# v1.net
KiCad netlist of a schematic drawn in EAGLE
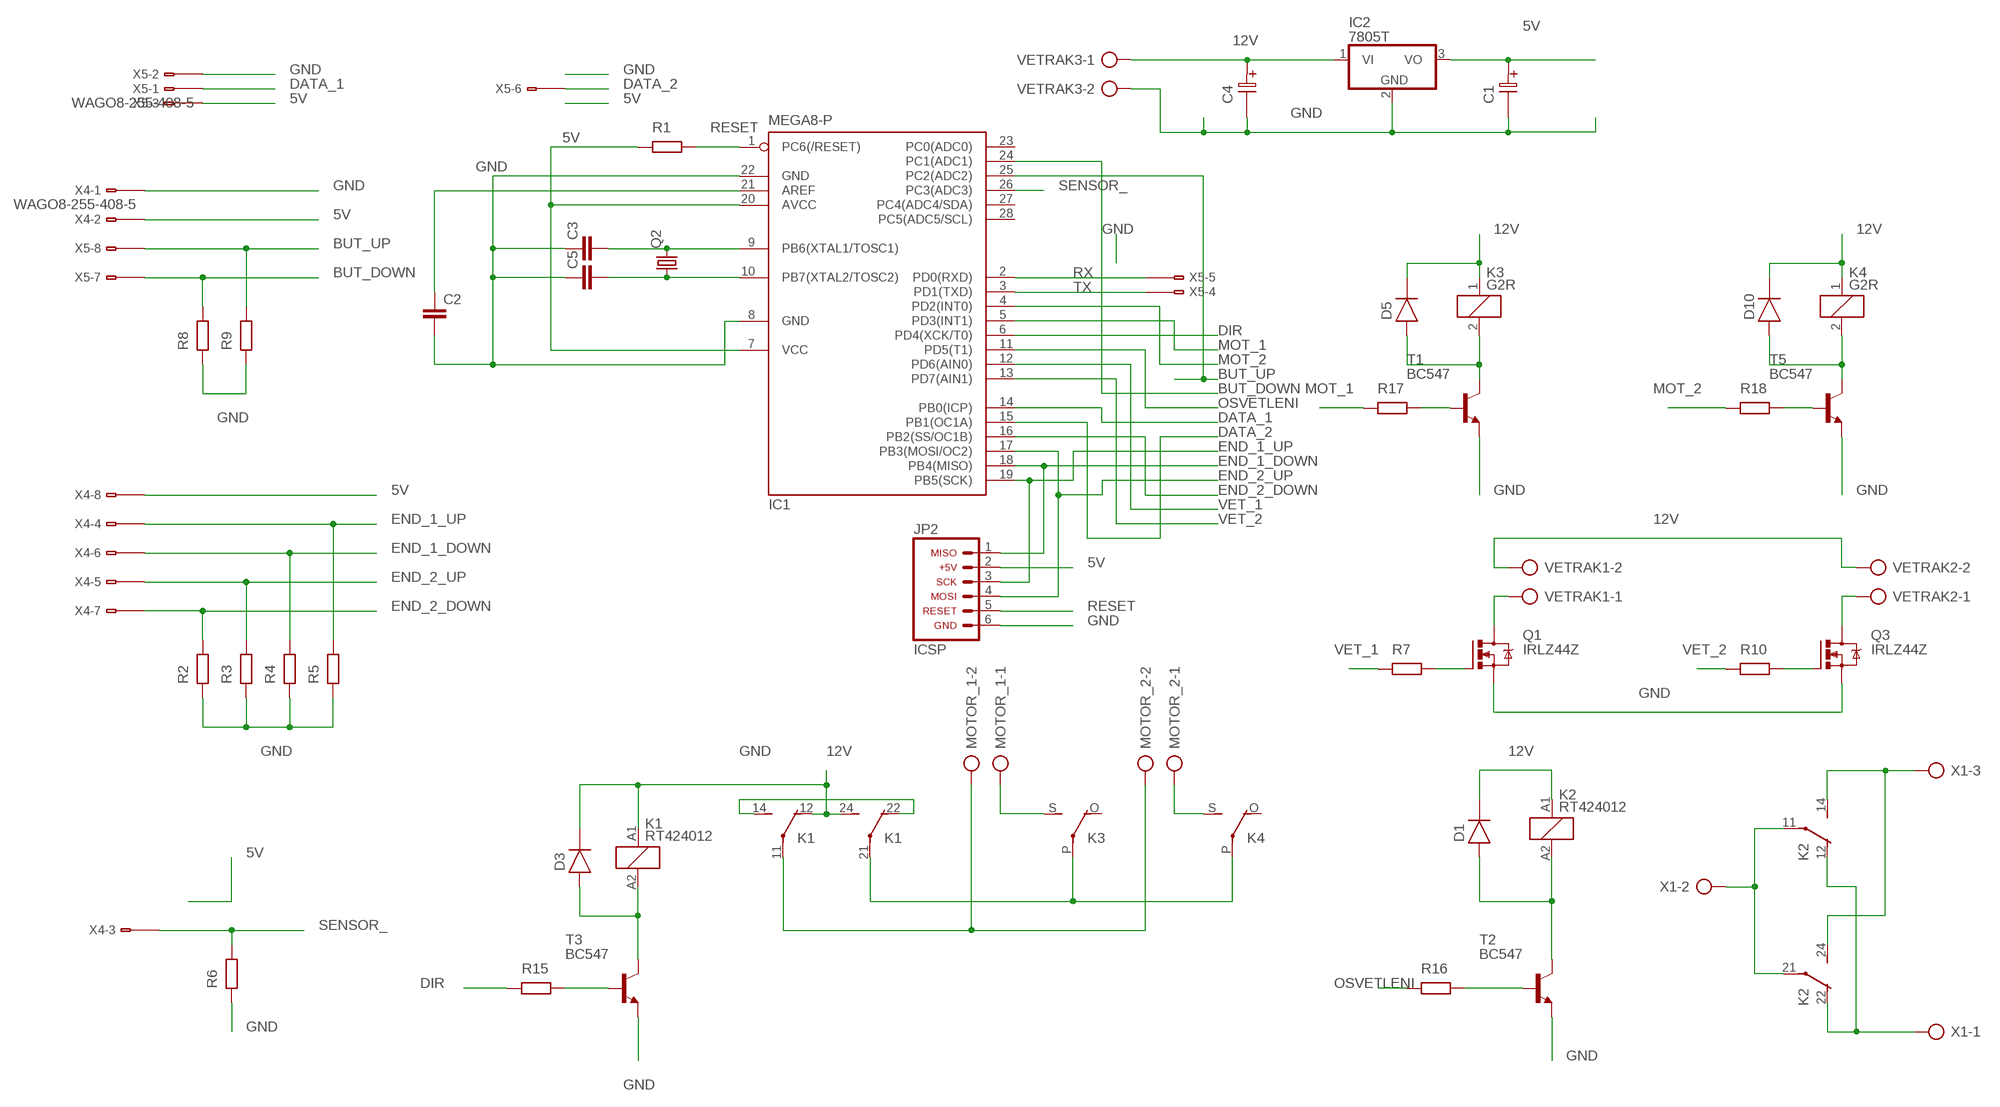
[diagram p0: schematic, sheet 1]

(export (version "E")
  (design (tool "Eeschema 10.0.6"))
  (components
    (comp (ref "C1")
      (value "CT12")
      (footprint "eagle-import:CT12")
      (libsource (lib "eagle-import") (part "CT12"))
    )
    (comp (ref "C2")
      (value "C-EU025-030X050")
      (footprint "eagle-import:C025-030X050")
      (libsource (lib "eagle-import") (part "C-EU025-030X050"))
    )
    (comp (ref "C3")
      (value "C-EU050-025X075")
      (footprint "eagle-import:C050-025X075")
      (libsource (lib "eagle-import") (part "C-EU050-025X075"))
    )
    (comp (ref "C4")
      (value "CT12")
      (footprint "eagle-import:CT12")
      (libsource (lib "eagle-import") (part "CT12"))
    )
    (comp (ref "C5")
      (value "C-EU050-025X075")
      (footprint "eagle-import:C050-025X075")
      (libsource (lib "eagle-import") (part "C-EU050-025X075"))
    )
    (comp (ref "D1")
      (value "1N4007")
      (footprint "eagle-import:DO41")
      (libsource (lib "eagle-import") (part "1N4007"))
    )
    (comp (ref "D3")
      (value "1N4007")
      (footprint "eagle-import:DO41")
      (libsource (lib "eagle-import") (part "1N4007"))
    )
    (comp (ref "D5")
      (value "1N4007")
      (footprint "eagle-import:DO41")
      (libsource (lib "eagle-import") (part "1N4007"))
    )
    (comp (ref "D10")
      (value "1N4007")
      (footprint "eagle-import:DO41")
      (libsource (lib "eagle-import") (part "1N4007"))
    )
    (comp (ref "IC1")
      (value "MEGA8-P")
      (footprint "eagle-import:DIL28-3")
      (libsource (lib "eagle-import") (part "MEGA8-P"))
    )
    (comp (ref "IC2")
      (value "7805T")
      (footprint "eagle-import:TO220H")
      (libsource (lib "eagle-import") (part "78T05"))
    )
    (comp (ref "JP2")
      (value "ARDUINO_CONN-ICSP")
      (footprint "eagle-import:CONN-2X03")
      (libsource (lib "eagle-import") (part "ARDUINO_CONN-ICSP"))
    )
    (comp (ref "K1")
      (value "RT424012")
      (footprint "eagle-import:RT2C_O")
      (libsource (lib "eagle-import") (part "RT42?4012"))
    )
    (comp (ref "K2")
      (value "RT424012")
      (footprint "eagle-import:RT2C_O")
      (libsource (lib "eagle-import") (part "RT42?4012"))
    )
    (comp (ref "K3")
      (value "G2R")
      (footprint "eagle-import:G2R")
      (libsource (lib "eagle-import") (part "G2R"))
    )
    (comp (ref "K4")
      (value "G2R")
      (footprint "eagle-import:G2R")
      (libsource (lib "eagle-import") (part "G2R"))
    )
    (comp (ref "MOTOR_1")
      (value "AK500/2")
      (footprint "eagle-import:AK500_2")
      (libsource (lib "eagle-import") (part "AK500/2"))
    )
    (comp (ref "MOTOR_2")
      (value "AK500/2")
      (footprint "eagle-import:AK500_2")
      (libsource (lib "eagle-import") (part "AK500/2"))
    )
    (comp (ref "Q1")
      (value "IRLZ44Z")
      (footprint "eagle-import:TO220BH")
      (libsource (lib "eagle-import") (part "IRLZ44Z"))
    )
    (comp (ref "Q2")
      (value "CRYSTALHC49S")
      (footprint "eagle-import:HC49_S")
      (libsource (lib "eagle-import") (part "CRYSTALHC49S"))
    )
    (comp (ref "Q3")
      (value "IRLZ44Z")
      (footprint "eagle-import:TO220BH")
      (libsource (lib "eagle-import") (part "IRLZ44Z"))
    )
    (comp (ref "R1") (value "RR") (footprint "eagle-import:RR") (libsource (lib "eagle-import") (part "RR")))
    (comp (ref "R2") (value "RR") (footprint "eagle-import:RR") (libsource (lib "eagle-import") (part "RR")))
    (comp (ref "R3") (value "RR") (footprint "eagle-import:RR") (libsource (lib "eagle-import") (part "RR")))
    (comp (ref "R4") (value "RR") (footprint "eagle-import:RR") (libsource (lib "eagle-import") (part "RR")))
    (comp (ref "R5") (value "RR") (footprint "eagle-import:RR") (libsource (lib "eagle-import") (part "RR")))
    (comp (ref "R6") (value "RR") (footprint "eagle-import:RR") (libsource (lib "eagle-import") (part "RR")))
    (comp (ref "R7") (value "RR") (footprint "eagle-import:RR") (libsource (lib "eagle-import") (part "RR")))
    (comp (ref "R8") (value "RR") (footprint "eagle-import:RR") (libsource (lib "eagle-import") (part "RR")))
    (comp (ref "R9") (value "RR") (footprint "eagle-import:RR") (libsource (lib "eagle-import") (part "RR")))
    (comp (ref "R10") (value "RR") (footprint "eagle-import:RR") (libsource (lib "eagle-import") (part "RR")))
    (comp (ref "R15") (value "RR") (footprint "eagle-import:RR") (libsource (lib "eagle-import") (part "RR")))
    (comp (ref "R16") (value "RR") (footprint "eagle-import:RR") (libsource (lib "eagle-import") (part "RR")))
    (comp (ref "R17") (value "RR") (footprint "eagle-import:RR") (libsource (lib "eagle-import") (part "RR")))
    (comp (ref "R18") (value "RR") (footprint "eagle-import:RR") (libsource (lib "eagle-import") (part "RR")))
    (comp (ref "T1")
      (value "BC547")
      (footprint "eagle-import:TO92")
      (libsource (lib "eagle-import") (part "BC547"))
    )
    (comp (ref "T2")
      (value "BC547")
      (footprint "eagle-import:TO92")
      (libsource (lib "eagle-import") (part "BC547"))
    )
    (comp (ref "T3")
      (value "BC547")
      (footprint "eagle-import:TO92")
      (libsource (lib "eagle-import") (part "BC547"))
    )
    (comp (ref "T5")
      (value "BC547")
      (footprint "eagle-import:TO92")
      (libsource (lib "eagle-import") (part "BC547"))
    )
    (comp (ref "VETRAK1")
      (value "AK500/2")
      (footprint "eagle-import:AK500_2")
      (libsource (lib "eagle-import") (part "AK500/2"))
    )
    (comp (ref "VETRAK2")
      (value "AK500/2")
      (footprint "eagle-import:AK500_2")
      (libsource (lib "eagle-import") (part "AK500/2"))
    )
    (comp (ref "VETRAK3")
      (value "AK500/2")
      (footprint "eagle-import:AK500_2")
      (libsource (lib "eagle-import") (part "AK500/2"))
    )
    (comp (ref "X1")
      (value "AK500/3-H")
      (footprint "eagle-import:AK500_3-H")
      (libsource (lib "eagle-import") (part "AK500/3-H"))
    )
    (comp (ref "X4")
      (value "WAGO8-255-408-5")
      (footprint "eagle-import:255-408-5")
      (fields (field (name "MPN") "255-408"))
      (libsource (lib "eagle-import") (part "WAGO8-255-408-5"))
    )
    (comp (ref "X5")
      (value "WAGO8-255-408-5")
      (footprint "eagle-import:255-408-5")
      (fields (field (name "MPN") "255-408"))
      (libsource (lib "eagle-import") (part "WAGO8-255-408-5"))
    )
  )
  (nets
    (net (code "1") (name "/5V") (class "Default")
      (node (ref "C1") (pin "1") (pinfunction "1_1") (pintype "passive"))
      (node (ref "IC1") (pin "20") (pinfunction "AVCC_20") (pintype "power_in"))
      (node (ref "IC1") (pin "7") (pinfunction "VCC_7") (pintype "power_in"))
      (node (ref "IC2") (pin "3") (pinfunction "VO_3") (pintype "passive"))
      (node (ref "JP2") (pin "2") (pinfunction "2_2") (pintype "passive"))
      (node (ref "R1") (pin "1") (pinfunction "1_1") (pintype "passive"))
      (node (ref "X4") (pin "B2") (pinfunction "B1_B2") (pintype "passive"))
      (node (ref "X4") (pin "B8") (pinfunction "B1_B8") (pintype "passive"))
      (node (ref "X5") (pin "B3") (pinfunction "B1_B3") (pintype "passive"))
    )
    (net (code "2") (name "/12V") (class "Default")
      (node (ref "C4") (pin "1") (pinfunction "1_1") (pintype "passive"))
      (node (ref "D1") (pin "K") (pinfunction "K_K") (pintype "passive"))
      (node (ref "D10") (pin "K") (pinfunction "K_K") (pintype "passive"))
      (node (ref "D3") (pin "K") (pinfunction "K_K") (pintype "passive"))
      (node (ref "D5") (pin "K") (pinfunction "K_K") (pintype "passive"))
      (node (ref "IC2") (pin "1") (pinfunction "VI_1") (pintype "input"))
      (node (ref "K1") (pin "12") (pinfunction "O_12") (pintype "passive"))
      (node (ref "K1") (pin "24") (pinfunction "S_24") (pintype "passive"))
      (node (ref "K1") (pin "A1") (pinfunction "1_A1") (pintype "passive"))
      (node (ref "K2") (pin "A1") (pinfunction "1_A1") (pintype "passive"))
      (node (ref "K3") (pin "1") (pinfunction "1_1") (pintype "passive"))
      (node (ref "K4") (pin "1") (pinfunction "1_1") (pintype "passive"))
      (node (ref "VETRAK1") (pin "2") (pinfunction "KL_2") (pintype "passive"))
      (node (ref "VETRAK2") (pin "2") (pinfunction "KL_2") (pintype "passive"))
      (node (ref "VETRAK3") (pin "1") (pinfunction "KL_1") (pintype "passive"))
    )
    (net (code "3") (name "/BUT_DOWN") (class "Default")
      (node (ref "IC1") (pin "24") (pinfunction "PC1(ADC1)_24") (pintype "bidirectional"))
      (node (ref "R8") (pin "2") (pinfunction "2_2") (pintype "passive"))
      (node (ref "X5") (pin "B7") (pinfunction "B1_B7") (pintype "passive"))
    )
    (net (code "4") (name "/BUT_UP") (class "Default")
      (node (ref "IC1") (pin "25") (pinfunction "PC2(ADC2)_25") (pintype "bidirectional"))
      (node (ref "R9") (pin "2") (pinfunction "2_2") (pintype "passive"))
      (node (ref "X5") (pin "B8") (pinfunction "B1_B8") (pintype "passive"))
    )
    (net (code "5") (name "/DATA_1") (class "Default")
      (node (ref "IC1") (pin "14") (pinfunction "PB0(ICP)_14") (pintype "bidirectional"))
      (node (ref "X5") (pin "B1") (pinfunction "B1_B1") (pintype "passive"))
    )
    (net (code "6") (name "/DATA_2") (class "Default")
      (node (ref "IC1") (pin "15") (pinfunction "PB1(OC1A)_15") (pintype "bidirectional"))
      (node (ref "X5") (pin "B6") (pinfunction "B1_B6") (pintype "passive"))
    )
    (net (code "7") (name "/DIR") (class "Default")
      (node (ref "IC1") (pin "6") (pinfunction "PD4(XCK/T0)_6") (pintype "bidirectional"))
      (node (ref "R15") (pin "1") (pinfunction "1_1") (pintype "passive"))
    )
    (net (code "8") (name "/END_1_DOWN") (class "Default")
      (node (ref "IC1") (pin "18") (pinfunction "PB4(MISO)_18") (pintype "bidirectional"))
      (node (ref "JP2") (pin "1") (pinfunction "1_1") (pintype "passive"))
      (node (ref "R4") (pin "2") (pinfunction "2_2") (pintype "passive"))
      (node (ref "X4") (pin "B6") (pinfunction "B1_B6") (pintype "passive"))
    )
    (net (code "9") (name "/END_1_UP") (class "Default")
      (node (ref "IC1") (pin "19") (pinfunction "PB5(SCK)_19") (pintype "bidirectional"))
      (node (ref "JP2") (pin "3") (pinfunction "3_3") (pintype "passive"))
      (node (ref "R5") (pin "2") (pinfunction "2_2") (pintype "passive"))
      (node (ref "X4") (pin "B4") (pinfunction "B1_B4") (pintype "passive"))
    )
    (net (code "10") (name "/END_2_DOWN") (class "Default")
      (node (ref "IC1") (pin "16") (pinfunction "PB2(SS/OC1B)_16") (pintype "bidirectional"))
      (node (ref "R2") (pin "2") (pinfunction "2_2") (pintype "passive"))
      (node (ref "X4") (pin "B7") (pinfunction "B1_B7") (pintype "passive"))
    )
    (net (code "11") (name "/END_2_UP") (class "Default")
      (node (ref "IC1") (pin "17") (pinfunction "PB3(MOSI/OC2)_17") (pintype "bidirectional"))
      (node (ref "JP2") (pin "4") (pinfunction "4_4") (pintype "passive"))
      (node (ref "R3") (pin "2") (pinfunction "2_2") (pintype "passive"))
      (node (ref "X4") (pin "B5") (pinfunction "B1_B5") (pintype "passive"))
    )
    (net (code "12") (name "/GND") (class "Default")
      (node (ref "C1") (pin "2") (pinfunction "2_2") (pintype "passive"))
      (node (ref "C2") (pin "2") (pinfunction "2_2") (pintype "passive"))
      (node (ref "C3") (pin "1") (pinfunction "1_1") (pintype "passive"))
      (node (ref "C4") (pin "2") (pinfunction "2_2") (pintype "passive"))
      (node (ref "C5") (pin "1") (pinfunction "1_1") (pintype "passive"))
      (node (ref "IC1") (pin "22") (pinfunction "GND_22") (pintype "power_in"))
      (node (ref "IC1") (pin "8") (pinfunction "GND_8") (pintype "power_in"))
      (node (ref "IC2") (pin "2") (pinfunction "GND_2") (pintype "passive"))
      (node (ref "JP2") (pin "6") (pinfunction "6_6") (pintype "passive"))
      (node (ref "K1") (pin "14") (pinfunction "S_14") (pintype "passive"))
      (node (ref "K1") (pin "22") (pinfunction "O_22") (pintype "passive"))
      (node (ref "Q1") (pin "S") (pinfunction "S_S") (pintype "passive"))
      (node (ref "Q3") (pin "S") (pinfunction "S_S") (pintype "passive"))
      (node (ref "R2") (pin "1") (pinfunction "1_1") (pintype "passive"))
      (node (ref "R3") (pin "1") (pinfunction "1_1") (pintype "passive"))
      (node (ref "R4") (pin "1") (pinfunction "1_1") (pintype "passive"))
      (node (ref "R5") (pin "1") (pinfunction "1_1") (pintype "passive"))
      (node (ref "R6") (pin "1") (pinfunction "1_1") (pintype "passive"))
      (node (ref "R8") (pin "1") (pinfunction "1_1") (pintype "passive"))
      (node (ref "R9") (pin "1") (pinfunction "1_1") (pintype "passive"))
      (node (ref "T1") (pin "1") (pinfunction "E_1") (pintype "passive"))
      (node (ref "T2") (pin "1") (pinfunction "E_1") (pintype "passive"))
      (node (ref "T3") (pin "1") (pinfunction "E_1") (pintype "passive"))
      (node (ref "T5") (pin "1") (pinfunction "E_1") (pintype "passive"))
      (node (ref "VETRAK3") (pin "2") (pinfunction "KL_2") (pintype "passive"))
      (node (ref "X4") (pin "B1") (pinfunction "B1_B1") (pintype "passive"))
      (node (ref "X5") (pin "B2") (pinfunction "B1_B2") (pintype "passive"))
    )
    (net (code "13") (name "/MOT_1") (class "Default")
      (node (ref "IC1") (pin "5") (pinfunction "PD3(INT1)_5") (pintype "bidirectional"))
      (node (ref "R17") (pin "1") (pinfunction "1_1") (pintype "passive"))
    )
    (net (code "14") (name "/MOT_2") (class "Default")
      (node (ref "IC1") (pin "4") (pinfunction "PD2(INT0)_4") (pintype "bidirectional"))
      (node (ref "R18") (pin "1") (pinfunction "1_1") (pintype "passive"))
    )
    (net (code "15") (name "/OSVETLENI") (class "Default")
      (node (ref "IC1") (pin "11") (pinfunction "PD5(T1)_11") (pintype "bidirectional"))
      (node (ref "R16") (pin "1") (pinfunction "1_1") (pintype "passive"))
    )
    (net (code "16") (name "/RESET") (class "Default")
      (node (ref "IC1") (pin "1") (pinfunction "PC6(/RESET)_1") (pintype "bidirectional"))
      (node (ref "JP2") (pin "5") (pinfunction "5_5") (pintype "passive"))
      (node (ref "R1") (pin "2") (pinfunction "2_2") (pintype "passive"))
    )
    (net (code "17") (name "/RX") (class "Default")
      (node (ref "IC1") (pin "2") (pinfunction "PD0(RXD)_2") (pintype "bidirectional"))
      (node (ref "X5") (pin "B5") (pinfunction "B1_B5") (pintype "passive"))
    )
    (net (code "18") (name "/SENSOR_") (class "Default")
      (node (ref "IC1") (pin "26") (pinfunction "PC3(ADC3)_26") (pintype "bidirectional"))
      (node (ref "R6") (pin "2") (pinfunction "2_2") (pintype "passive"))
      (node (ref "X4") (pin "B3") (pinfunction "B1_B3") (pintype "passive"))
    )
    (net (code "19") (name "/TX") (class "Default")
      (node (ref "IC1") (pin "3") (pinfunction "PD1(TXD)_3") (pintype "bidirectional"))
      (node (ref "X5") (pin "B4") (pinfunction "B1_B4") (pintype "passive"))
    )
    (net (code "20") (name "/VET_1") (class "Default")
      (node (ref "IC1") (pin "12") (pinfunction "PD6(AIN0)_12") (pintype "bidirectional"))
      (node (ref "R7") (pin "1") (pinfunction "1_1") (pintype "passive"))
    )
    (net (code "21") (name "/VET_2") (class "Default")
      (node (ref "IC1") (pin "13") (pinfunction "PD7(AIN1)_13") (pintype "bidirectional"))
      (node (ref "R10") (pin "1") (pinfunction "1_1") (pintype "passive"))
    )
    (net (code "22") (name "Net-(IC1-AREF)") (class "Default")
      (node (ref "C2") (pin "1") (pinfunction "1_1") (pintype "passive"))
      (node (ref "IC1") (pin "21") (pinfunction "AREF_21") (pintype "passive"))
    )
    (net (code "23") (name "Net-(IC1-PB6(XTAL1{slash}TOSC1))") (class "Default")
      (node (ref "C3") (pin "2") (pinfunction "2_2") (pintype "passive"))
      (node (ref "IC1") (pin "9") (pinfunction "PB6(XTAL1/TOSC1)_9") (pintype "bidirectional"))
      (node (ref "Q2") (pin "2") (pinfunction "2_2") (pintype "passive"))
    )
    (net (code "24") (name "Net-(IC1-PB7(XTAL2{slash}TOSC2))") (class "Default")
      (node (ref "C5") (pin "2") (pinfunction "2_2") (pintype "passive"))
      (node (ref "IC1") (pin "10") (pinfunction "PB7(XTAL2/TOSC2)_10") (pintype "bidirectional"))
      (node (ref "Q2") (pin "1") (pinfunction "1_1") (pintype "passive"))
    )
    (net (code "25") (name "Net-(K1A-2)") (class "Default")
      (node (ref "D3") (pin "A") (pinfunction "A_A") (pintype "passive"))
      (node (ref "K1") (pin "A2") (pinfunction "2_A2") (pintype "passive"))
      (node (ref "T3") (pin "3") (pinfunction "C_3") (pintype "passive"))
    )
    (net (code "26") (name "Net-(K1B-P)") (class "Default")
      (node (ref "K1") (pin "11") (pinfunction "P_11") (pintype "passive"))
      (node (ref "MOTOR_1") (pin "2") (pinfunction "KL_2") (pintype "passive"))
      (node (ref "MOTOR_2") (pin "2") (pinfunction "KL_2") (pintype "passive"))
    )
    (net (code "27") (name "Net-(K1C-P)") (class "Default")
      (node (ref "K1") (pin "21") (pinfunction "P_21") (pintype "passive"))
      (node (ref "K3") (pin "P") (pinfunction "P_P") (pintype "passive"))
      (node (ref "K4") (pin "P") (pinfunction "P_P") (pintype "passive"))
    )
    (net (code "28") (name "Net-(K2A-2)") (class "Default")
      (node (ref "D1") (pin "A") (pinfunction "A_A") (pintype "passive"))
      (node (ref "K2") (pin "A2") (pinfunction "2_A2") (pintype "passive"))
      (node (ref "T2") (pin "3") (pinfunction "C_3") (pintype "passive"))
    )
    (net (code "29") (name "Net-(K2B-O)") (class "Default")
      (node (ref "K2") (pin "12") (pinfunction "O_12") (pintype "passive"))
      (node (ref "K2") (pin "22") (pinfunction "O_22") (pintype "passive"))
      (node (ref "X1") (pin "1") (pinfunction "KL_1") (pintype "passive"))
    )
    (net (code "30") (name "Net-(K2B-P)") (class "Default")
      (node (ref "K2") (pin "11") (pinfunction "P_11") (pintype "passive"))
      (node (ref "K2") (pin "21") (pinfunction "P_21") (pintype "passive"))
      (node (ref "X1") (pin "2") (pinfunction "KL_2") (pintype "passive"))
    )
    (net (code "31") (name "Net-(K2B-S)") (class "Default")
      (node (ref "K2") (pin "14") (pinfunction "S_14") (pintype "passive"))
      (node (ref "K2") (pin "24") (pinfunction "S_24") (pintype "passive"))
      (node (ref "X1") (pin "3") (pinfunction "KL_3") (pintype "passive"))
    )
    (net (code "32") (name "Net-(MOTOR_1A-KL)") (class "Default")
      (node (ref "K3") (pin "S") (pinfunction "S_S") (pintype "passive"))
      (node (ref "MOTOR_1") (pin "1") (pinfunction "KL_1") (pintype "passive"))
    )
    (net (code "33") (name "Net-(MOTOR_2A-KL)") (class "Default")
      (node (ref "K4") (pin "S") (pinfunction "S_S") (pintype "passive"))
      (node (ref "MOTOR_2") (pin "1") (pinfunction "KL_1") (pintype "passive"))
    )
    (net (code "34") (name "Net-(Q1-PadG)") (class "Default")
      (node (ref "Q1") (pin "G") (pinfunction "G_G") (pintype "passive"))
      (node (ref "R7") (pin "2") (pinfunction "2_2") (pintype "passive"))
    )
    (net (code "35") (name "Net-(Q3-PadG)") (class "Default")
      (node (ref "Q3") (pin "G") (pinfunction "G_G") (pintype "passive"))
      (node (ref "R10") (pin "2") (pinfunction "2_2") (pintype "passive"))
    )
    (net (code "36") (name "Net-(T1-B)") (class "Default")
      (node (ref "R17") (pin "2") (pinfunction "2_2") (pintype "passive"))
      (node (ref "T1") (pin "2") (pinfunction "B_2") (pintype "passive"))
    )
    (net (code "37") (name "Net-(T1-C)") (class "Default")
      (node (ref "D5") (pin "A") (pinfunction "A_A") (pintype "passive"))
      (node (ref "K3") (pin "2") (pinfunction "2_2") (pintype "passive"))
      (node (ref "T1") (pin "3") (pinfunction "C_3") (pintype "passive"))
    )
    (net (code "38") (name "Net-(T2-B)") (class "Default")
      (node (ref "R16") (pin "2") (pinfunction "2_2") (pintype "passive"))
      (node (ref "T2") (pin "2") (pinfunction "B_2") (pintype "passive"))
    )
    (net (code "39") (name "Net-(T3-B)") (class "Default")
      (node (ref "R15") (pin "2") (pinfunction "2_2") (pintype "passive"))
      (node (ref "T3") (pin "2") (pinfunction "B_2") (pintype "passive"))
    )
    (net (code "40") (name "Net-(T5-B)") (class "Default")
      (node (ref "R18") (pin "2") (pinfunction "2_2") (pintype "passive"))
      (node (ref "T5") (pin "2") (pinfunction "B_2") (pintype "passive"))
    )
    (net (code "41") (name "Net-(T5-C)") (class "Default")
      (node (ref "D10") (pin "A") (pinfunction "A_A") (pintype "passive"))
      (node (ref "K4") (pin "2") (pinfunction "2_2") (pintype "passive"))
      (node (ref "T5") (pin "3") (pinfunction "C_3") (pintype "passive"))
    )
    (net (code "42") (name "Net-(VETRAK1A-KL)") (class "Default")
      (node (ref "Q1") (pin "D") (pinfunction "D_D") (pintype "passive"))
      (node (ref "VETRAK1") (pin "1") (pinfunction "KL_1") (pintype "passive"))
    )
    (net (code "43") (name "Net-(VETRAK2A-KL)") (class "Default")
      (node (ref "Q3") (pin "D") (pinfunction "D_D") (pintype "passive"))
      (node (ref "VETRAK2") (pin "1") (pinfunction "KL_1") (pintype "passive"))
    )
    (net (code "44") (name "unconnected-(IC1-PC0(ADC0)-Pad23)") (class "Default")
      (node (ref "IC1") (pin "23") (pinfunction "PC0(ADC0)_23") (pintype "bidirectional"))
    )
    (net (code "45") (name "unconnected-(IC1-PC4(ADC4{slash}SDA)-Pad27)") (class "Default")
      (node (ref "IC1") (pin "27") (pinfunction "PC4(ADC4/SDA)_27") (pintype "bidirectional"))
    )
    (net (code "46") (name "unconnected-(IC1-PC5(ADC5{slash}SCL)-Pad28)") (class "Default")
      (node (ref "IC1") (pin "28") (pinfunction "PC5(ADC5/SCL)_28") (pintype "bidirectional"))
    )
    (net (code "47") (name "unconnected-(K3-PadO)") (class "Default")
      (node (ref "K3") (pin "O") (pinfunction "O_O") (pintype "passive"))
    )
    (net (code "48") (name "unconnected-(K4-PadO)") (class "Default")
      (node (ref "K4") (pin "O") (pinfunction "O_O") (pintype "passive"))
    )
    (net (code "49") (name "unconnected-(X4-PadA1)") (class "Default")
      (node (ref "X4") (pin "A1") (pinfunction "A1_A1") (pintype "passive"))
    )
    (net (code "50") (name "unconnected-(X4B-A1-PadA2)") (class "Default")
      (node (ref "X4") (pin "A2") (pinfunction "A1_A2") (pintype "passive"))
    )
    (net (code "51") (name "unconnected-(X4C-A1-PadA3)") (class "Default")
      (node (ref "X4") (pin "A3") (pinfunction "A1_A3") (pintype "passive"))
    )
    (net (code "52") (name "unconnected-(X4D-A1-PadA4)") (class "Default")
      (node (ref "X4") (pin "A4") (pinfunction "A1_A4") (pintype "passive"))
    )
    (net (code "53") (name "unconnected-(X4E-A1-PadA5)") (class "Default")
      (node (ref "X4") (pin "A5") (pinfunction "A1_A5") (pintype "passive"))
    )
    (net (code "54") (name "unconnected-(X4F-A1-PadA6)") (class "Default")
      (node (ref "X4") (pin "A6") (pinfunction "A1_A6") (pintype "passive"))
    )
    (net (code "55") (name "unconnected-(X4G-A1-PadA7)") (class "Default")
      (node (ref "X4") (pin "A7") (pinfunction "A1_A7") (pintype "passive"))
    )
    (net (code "56") (name "unconnected-(X4H-A1-PadA8)") (class "Default")
      (node (ref "X4") (pin "A8") (pinfunction "A1_A8") (pintype "passive"))
    )
    (net (code "57") (name "unconnected-(X5-PadA1)") (class "Default")
      (node (ref "X5") (pin "A1") (pinfunction "A1_A1") (pintype "passive"))
    )
    (net (code "58") (name "unconnected-(X5B-A1-PadA2)") (class "Default")
      (node (ref "X5") (pin "A2") (pinfunction "A1_A2") (pintype "passive"))
    )
    (net (code "59") (name "unconnected-(X5C-A1-PadA3)") (class "Default")
      (node (ref "X5") (pin "A3") (pinfunction "A1_A3") (pintype "passive"))
    )
    (net (code "60") (name "unconnected-(X5D-A1-PadA4)") (class "Default")
      (node (ref "X5") (pin "A4") (pinfunction "A1_A4") (pintype "passive"))
    )
    (net (code "61") (name "unconnected-(X5E-A1-PadA5)") (class "Default")
      (node (ref "X5") (pin "A5") (pinfunction "A1_A5") (pintype "passive"))
    )
    (net (code "62") (name "unconnected-(X5F-A1-PadA6)") (class "Default")
      (node (ref "X5") (pin "A6") (pinfunction "A1_A6") (pintype "passive"))
    )
    (net (code "63") (name "unconnected-(X5G-A1-PadA7)") (class "Default")
      (node (ref "X5") (pin "A7") (pinfunction "A1_A7") (pintype "passive"))
    )
    (net (code "64") (name "unconnected-(X5H-A1-PadA8)") (class "Default")
      (node (ref "X5") (pin "A8") (pinfunction "A1_A8") (pintype "passive"))
    )
  )
)
